# DC_DC_5V_1.net
KiCad netlist of a schematic drawn in Altium Designer
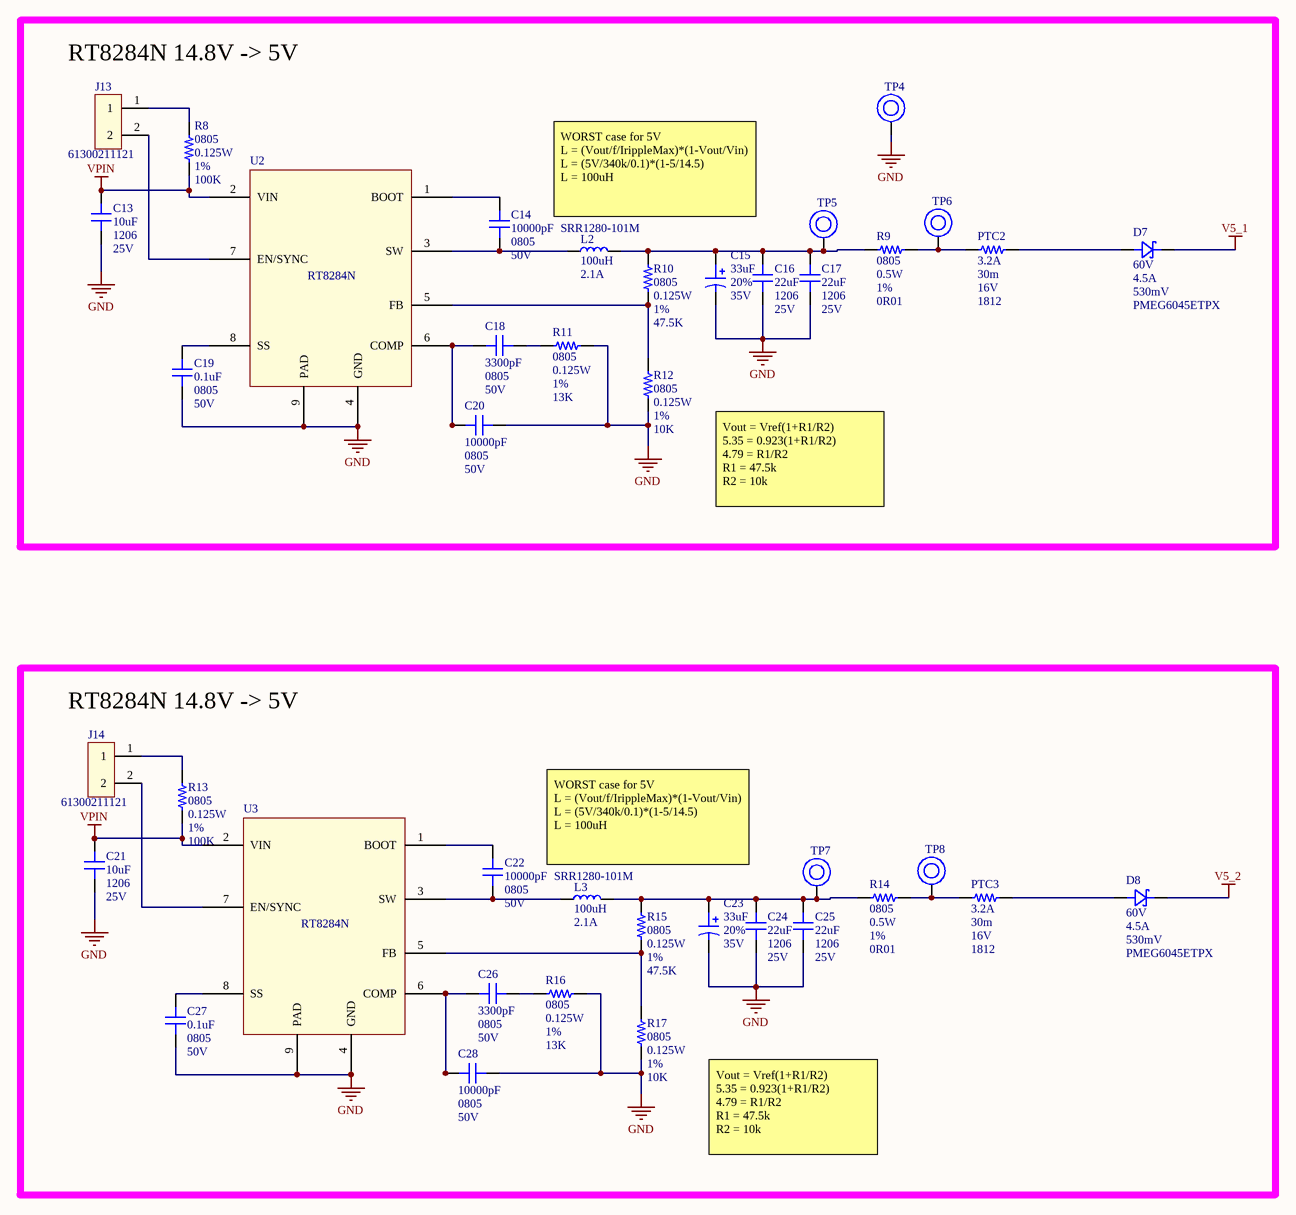
[diagram p0: DC_DC_5V_1.SchDoc]

(export (version "E")
  (design (tool "Eeschema 10.0.6"))
  (components
    (comp (ref "C13")
      (value "10uF")
      (footprint "CAP_1206")
      (description "CAP CER 10uF 25V 1206")
      (fields
        (field (name "PART NUMBER") "CL31A106KAHNFNE‎")
        (field (name "PACKAGE") "1206")
        (field (name "VOLTAGE") "25V")
        (field (name "Comment") "CAP_‎CL31A106KAHNFNE‎")
      )
      (libsource (lib "SecureBot") (part "CAP_‎CL31A106KAHNFNE‎"))
    )
    (comp (ref "C14")
      (value "10000pF")
      (footprint "CAP_0805")
      (description "CAP CER 10000pF 50V 0805")
      (fields
        (field (name "PART NUMBER") "‎CL21B103KBANNNC")
        (field (name "PACKAGE") "0805")
        (field (name "VOLTAGE") "50V")
        (field (name "Comment") "CAP_‎‎‎‎CL21B103KBANNNC")
      )
      (libsource (lib "SecureBot") (part "CAP_‎‎‎‎CL21B103KBANNNC"))
    )
    (comp (ref "C15")
      (value "33uF")
      (footprint "CAP ALU - 6.3mm DIA")
      (description "CAP ALU 33µF 35V")
      (fields
        (field (name "PART NUMBER") "EEE-FK1V330P")
        (field (name "TOLERANCE") "20%")
        (field (name "VOLTAGE") "35V")
        (field (name "Comment") "CAP_EEE-FK1V330P")
      )
      (libsource (lib "SecureBot") (part "CAP_EEE-FK1V330P"))
    )
    (comp (ref "C16")
      (value "22uF")
      (footprint "CAP_1206")
      (description "CAP CER 22uF 25V 1206")
      (fields
        (field (name "PART NUMBER") "CL31A226KAHNNNE‎")
        (field (name "PACKAGE") "1206")
        (field (name "VOLTAGE") "25V")
        (field (name "Comment") "CAP_‎‎CL31A226KAHNNNE‎")
      )
      (libsource (lib "SecureBot") (part "CAP_‎‎CL31A226KAHNNNE‎"))
    )
    (comp (ref "C17")
      (value "22uF")
      (footprint "CAP_1206")
      (description "CAP CER 22uF 25V 1206")
      (fields
        (field (name "PART NUMBER") "CL31A226KAHNNNE‎")
        (field (name "PACKAGE") "1206")
        (field (name "VOLTAGE") "25V")
        (field (name "Comment") "CAP_‎‎CL31A226KAHNNNE‎")
      )
      (libsource (lib "SecureBot") (part "CAP_‎‎CL31A226KAHNNNE‎"))
    )
    (comp (ref "C18")
      (value "3300pF")
      (footprint "CAP_0805")
      (description "CAP CER 3300pF 50V 0805")
      (fields
        (field (name "PART NUMBER") "CL21B332KBANNNC‎")
        (field (name "PACKAGE") "0805")
        (field (name "VOLTAGE") "50V")
        (field (name "Comment") "CAP_CL21B332KBANNNC‎")
      )
      (libsource (lib "SecureBot") (part "CAP_CL21B332KBANNNC‎"))
    )
    (comp (ref "C19")
      (value "0.1uF")
      (footprint "CAP_0805")
      (description "CAP CER 0.1uF 50V 0805")
      (fields
        (field (name "PART NUMBER") "CC0805KRX7R9BB104‎")
        (field (name "PACKAGE") "0805")
        (field (name "VOLTAGE") "50V")
        (field (name "Comment") "CAP_CC0805KRX7R9BB104‎")
      )
      (libsource (lib "SecureBot") (part "CAP_CC0805KRX7R9BB104‎"))
    )
    (comp (ref "C20")
      (value "10000pF")
      (footprint "CAP_0805")
      (description "CAP CER 10000pF 50V 0805")
      (fields
        (field (name "PART NUMBER") "‎CL21B103KBANNNC")
        (field (name "PACKAGE") "0805")
        (field (name "VOLTAGE") "50V")
        (field (name "Comment") "CAP_‎‎‎‎CL21B103KBANNNC")
      )
      (libsource (lib "SecureBot") (part "CAP_‎‎‎‎CL21B103KBANNNC"))
    )
    (comp (ref "C21")
      (value "10uF")
      (footprint "CAP_1206")
      (description "CAP CER 10uF 25V 1206")
      (fields
        (field (name "PART NUMBER") "CL31A106KAHNFNE‎")
        (field (name "PACKAGE") "1206")
        (field (name "VOLTAGE") "25V")
        (field (name "Comment") "CAP_‎CL31A106KAHNFNE‎")
      )
      (libsource (lib "SecureBot") (part "CAP_‎CL31A106KAHNFNE‎"))
    )
    (comp (ref "C22")
      (value "10000pF")
      (footprint "CAP_0805")
      (description "CAP CER 10000pF 50V 0805")
      (fields
        (field (name "PART NUMBER") "‎CL21B103KBANNNC")
        (field (name "PACKAGE") "0805")
        (field (name "VOLTAGE") "50V")
        (field (name "Comment") "CAP_‎‎‎‎CL21B103KBANNNC")
      )
      (libsource (lib "SecureBot") (part "CAP_‎‎‎‎CL21B103KBANNNC"))
    )
    (comp (ref "C23")
      (value "33uF")
      (footprint "CAP ALU - 6.3mm DIA")
      (description "CAP ALU 33µF 35V")
      (fields
        (field (name "PART NUMBER") "EEE-FK1V330P")
        (field (name "TOLERANCE") "20%")
        (field (name "VOLTAGE") "35V")
        (field (name "Comment") "CAP_EEE-FK1V330P")
      )
      (libsource (lib "SecureBot") (part "CAP_EEE-FK1V330P"))
    )
    (comp (ref "C24")
      (value "22uF")
      (footprint "CAP_1206")
      (description "CAP CER 22uF 25V 1206")
      (fields
        (field (name "PART NUMBER") "CL31A226KAHNNNE‎")
        (field (name "PACKAGE") "1206")
        (field (name "VOLTAGE") "25V")
        (field (name "Comment") "CAP_‎‎CL31A226KAHNNNE‎")
      )
      (libsource (lib "SecureBot") (part "CAP_‎‎CL31A226KAHNNNE‎"))
    )
    (comp (ref "C25")
      (value "22uF")
      (footprint "CAP_1206")
      (description "CAP CER 22uF 25V 1206")
      (fields
        (field (name "PART NUMBER") "CL31A226KAHNNNE‎")
        (field (name "PACKAGE") "1206")
        (field (name "VOLTAGE") "25V")
        (field (name "Comment") "CAP_‎‎CL31A226KAHNNNE‎")
      )
      (libsource (lib "SecureBot") (part "CAP_‎‎CL31A226KAHNNNE‎"))
    )
    (comp (ref "C26")
      (value "3300pF")
      (footprint "CAP_0805")
      (description "CAP CER 3300pF 50V 0805")
      (fields
        (field (name "PART NUMBER") "CL21B332KBANNNC‎")
        (field (name "PACKAGE") "0805")
        (field (name "VOLTAGE") "50V")
        (field (name "Comment") "CAP_CL21B332KBANNNC‎")
      )
      (libsource (lib "SecureBot") (part "CAP_CL21B332KBANNNC‎"))
    )
    (comp (ref "C27")
      (value "0.1uF")
      (footprint "CAP_0805")
      (description "CAP CER 0.1uF 50V 0805")
      (fields
        (field (name "PART NUMBER") "CC0805KRX7R9BB104‎")
        (field (name "PACKAGE") "0805")
        (field (name "VOLTAGE") "50V")
        (field (name "Comment") "CAP_CC0805KRX7R9BB104‎")
      )
      (libsource (lib "SecureBot") (part "CAP_CC0805KRX7R9BB104‎"))
    )
    (comp (ref "C28")
      (value "10000pF")
      (footprint "CAP_0805")
      (description "CAP CER 10000pF 50V 0805")
      (fields
        (field (name "PART NUMBER") "‎CL21B103KBANNNC")
        (field (name "PACKAGE") "0805")
        (field (name "VOLTAGE") "50V")
        (field (name "Comment") "CAP_‎‎‎‎CL21B103KBANNNC")
      )
      (libsource (lib "SecureBot") (part "CAP_‎‎‎‎CL21B103KBANNNC"))
    )
    (comp (ref "D7")
      (value "DIODE_SCH_PMEG6045ETPX")
      (footprint "DO-214AC_SOD128")
      (description "Diode Schottky 60V 4.5A Surface Mount CFP5")
      (fields
        (field (name "VOLTAGE") "60V")
        (field (name "CURRENT") "4.5A")
        (field (name "VF") "530mV")
        (field (name "PART NUMBER") "PMEG6045ETPX")
      )
      (libsource (lib "SecureBot") (part "DIODE_SCH_PMEG6045ETPX"))
    )
    (comp (ref "D8")
      (value "DIODE_SCH_PMEG6045ETPX")
      (footprint "DO-214AC_SOD128")
      (description "Diode Schottky 60V 4.5A Surface Mount CFP5")
      (fields
        (field (name "VOLTAGE") "60V")
        (field (name "CURRENT") "4.5A")
        (field (name "VF") "530mV")
        (field (name "PART NUMBER") "PMEG6045ETPX")
      )
      (libsource (lib "SecureBot") (part "DIODE_SCH_PMEG6045ETPX"))
    )
    (comp (ref "J13")
      (value "Header 2 pin SM")
      (footprint "HDR1X2")
      (fields (field (name "PART NUMBER") "61300211121"))
      (libsource (lib "SecureBot") (part "Header 2 pin SM"))
    )
    (comp (ref "J14")
      (value "Header 2 pin SM")
      (footprint "HDR1X2")
      (fields (field (name "PART NUMBER") "61300211121"))
      (libsource (lib "SecureBot") (part "Header 2 pin SM"))
    )
    (comp (ref "L2")
      (value "100uH")
      (footprint "BOURNS 12.5x12.5mm")
      (description "IND 100µH Shielded Wirewound Inductor 2.1A")
      (fields
        (field (name "TOLERANCE") "20%")
        (field (name "CURRENT") "2.1A")
        (field (name "PART NUMBER") "SRR1280-101M")
        (field (name "Comment") "IND_SRR1280-101M")
      )
      (libsource (lib "SecureBot") (part "IND_SRR1280-101M"))
    )
    (comp (ref "L3")
      (value "100uH")
      (footprint "BOURNS 12.5x12.5mm")
      (description "IND 100µH Shielded Wirewound Inductor 2.1A")
      (fields
        (field (name "TOLERANCE") "20%")
        (field (name "CURRENT") "2.1A")
        (field (name "PART NUMBER") "SRR1280-101M")
        (field (name "Comment") "IND_SRR1280-101M")
      )
      (libsource (lib "SecureBot") (part "IND_SRR1280-101M"))
    )
    (comp (ref "PTC2")
      (value "PTC_0ZCG0160BF2C")
      (footprint "PTC - 1812")
      (description "PTC_Polymeric PTC Resettable Fuse 16V 1.6A Ih")
      (fields
        (field (name "PART NUMBER") "0ZCG0160BF2C")
        (field (name "TRIP VALUE") "3.2A")
        (field (name "RES") "30m")
        (field (name "VOLTAGE") "16V")
        (field (name "PACKAGE") "1812")
      )
      (libsource (lib "SecureBot") (part "PTC_0ZCG0160BF2C"))
    )
    (comp (ref "PTC3")
      (value "PTC_0ZCG0160BF2C")
      (footprint "PTC - 1812")
      (description "PTC_Polymeric PTC Resettable Fuse 16V 1.6A Ih")
      (fields
        (field (name "PART NUMBER") "0ZCG0160BF2C")
        (field (name "TRIP VALUE") "3.2A")
        (field (name "RES") "30m")
        (field (name "VOLTAGE") "16V")
        (field (name "PACKAGE") "1812")
      )
      (libsource (lib "SecureBot") (part "PTC_0ZCG0160BF2C"))
    )
    (comp (ref "R8")
      (value "100K")
      (footprint "RES_0805")
      (description "RES 100K 1% 1/8W 0805")
      (fields
        (field (name "PART NUMBER") "‎RMCF0805FT100K‎")
        (field (name "PACKAGE") "0805")
        (field (name "POWER") "0.125W")
        (field (name "TOLERANCE") "1%")
        (field (name "Comment") "RES_‎RMCF0805FT100K‎")
      )
      (libsource (lib "SecureBot") (part "RES_‎RMCF0805FT100K‎"))
    )
    (comp (ref "R9")
      (value "0R01")
      (footprint "RES_0805")
      (description "RES 0.01R 1% 1/2W 0805")
      (fields
        (field (name "PART NUMBER") "KRL1220E-M-R010-F-T5")
        (field (name "PACKAGE") "0805")
        (field (name "POWER") "0.5W")
        (field (name "TOLERANCE") "1%")
        (field (name "Comment") "RES_‎‎‎‎‎ KRL1220E-M-R010-F-T5")
      )
      (libsource (lib "SecureBot") (part "RES_‎‎‎‎‎ KRL1220E-M-R010-F-T5"))
    )
    (comp (ref "R10")
      (value "47.5K")
      (footprint "RES_0805")
      (description "RES 47.5K 1% 1/8W 0805")
      (fields
        (field (name "PART NUMBER") "RMCF0805FT47K5‎")
        (field (name "PACKAGE") "0805")
        (field (name "POWER") "0.125W")
        (field (name "TOLERANCE") "1%")
        (field (name "Comment") "RES_‎‎RMCF0805FT47K5‎")
      )
      (libsource (lib "SecureBot") (part "RES_‎‎RMCF0805FT47K5‎"))
    )
    (comp (ref "R11")
      (value "13K")
      (footprint "RES_0805")
      (description "RES 13K 1% 1/8W 0805")
      (fields
        (field (name "PART NUMBER") "RC0805FR-0713KL")
        (field (name "PACKAGE") "0805")
        (field (name "POWER") "0.125W")
        (field (name "TOLERANCE") "1%")
        (field (name "Comment") "RES_‎ RC0805FR-0713KL")
      )
      (libsource (lib "SecureBot") (part "RES_‎ RC0805FR-0713KL"))
    )
    (comp (ref "R12")
      (value "10K")
      (footprint "RES_0805")
      (description "RES 10K 1% 1/8W 0805")
      (fields
        (field (name "PART NUMBER") "RMCF0805FT10K0")
        (field (name "PACKAGE") "0805")
        (field (name "POWER") "0.125W")
        (field (name "TOLERANCE") "1%")
        (field (name "Comment") "RES_‎RMCF0805FT10K0")
      )
      (libsource (lib "SecureBot") (part "RES_‎RMCF0805FT10K0"))
    )
    (comp (ref "R13")
      (value "100K")
      (footprint "RES_0805")
      (description "RES 100K 1% 1/8W 0805")
      (fields
        (field (name "PART NUMBER") "‎RMCF0805FT100K‎")
        (field (name "PACKAGE") "0805")
        (field (name "POWER") "0.125W")
        (field (name "TOLERANCE") "1%")
        (field (name "Comment") "RES_‎RMCF0805FT100K‎")
      )
      (libsource (lib "SecureBot") (part "RES_‎RMCF0805FT100K‎"))
    )
    (comp (ref "R14")
      (value "0R01")
      (footprint "RES_0805")
      (description "RES 0.01R 1% 1/2W 0805")
      (fields
        (field (name "PART NUMBER") "KRL1220E-M-R010-F-T5")
        (field (name "PACKAGE") "0805")
        (field (name "POWER") "0.5W")
        (field (name "TOLERANCE") "1%")
        (field (name "Comment") "RES_‎‎‎‎‎ KRL1220E-M-R010-F-T5")
      )
      (libsource (lib "SecureBot") (part "RES_‎‎‎‎‎ KRL1220E-M-R010-F-T5"))
    )
    (comp (ref "R15")
      (value "47.5K")
      (footprint "RES_0805")
      (description "RES 47.5K 1% 1/8W 0805")
      (fields
        (field (name "PART NUMBER") "RMCF0805FT47K5‎")
        (field (name "PACKAGE") "0805")
        (field (name "POWER") "0.125W")
        (field (name "TOLERANCE") "1%")
        (field (name "Comment") "RES_‎‎RMCF0805FT47K5‎")
      )
      (libsource (lib "SecureBot") (part "RES_‎‎RMCF0805FT47K5‎"))
    )
    (comp (ref "R16")
      (value "13K")
      (footprint "RES_0805")
      (description "RES 13K 1% 1/8W 0805")
      (fields
        (field (name "PART NUMBER") "RC0805FR-0713KL")
        (field (name "PACKAGE") "0805")
        (field (name "POWER") "0.125W")
        (field (name "TOLERANCE") "1%")
        (field (name "Comment") "RES_‎ RC0805FR-0713KL")
      )
      (libsource (lib "SecureBot") (part "RES_‎ RC0805FR-0713KL"))
    )
    (comp (ref "R17")
      (value "10K")
      (footprint "RES_0805")
      (description "RES 10K 1% 1/8W 0805")
      (fields
        (field (name "PART NUMBER") "RMCF0805FT10K0")
        (field (name "PACKAGE") "0805")
        (field (name "POWER") "0.125W")
        (field (name "TOLERANCE") "1%")
        (field (name "Comment") "RES_‎RMCF0805FT10K0")
      )
      (libsource (lib "SecureBot") (part "RES_‎RMCF0805FT10K0"))
    )
    (comp (ref "TP4")
      (value "TestPoint 3x3mm")
      (footprint "TestPoint 3X3mm")
      (libsource (lib "SecureBot") (part "TestPoint 3x3mm"))
    )
    (comp (ref "TP5")
      (value "TestPoint 3x3mm")
      (footprint "TestPoint 3X3mm")
      (libsource (lib "SecureBot") (part "TestPoint 3x3mm"))
    )
    (comp (ref "TP6")
      (value "TestPoint 3x3mm")
      (footprint "TestPoint 3X3mm")
      (libsource (lib "SecureBot") (part "TestPoint 3x3mm"))
    )
    (comp (ref "TP7")
      (value "TestPoint 3x3mm")
      (footprint "TestPoint 3X3mm")
      (libsource (lib "SecureBot") (part "TestPoint 3x3mm"))
    )
    (comp (ref "TP8")
      (value "TestPoint 3x3mm")
      (footprint "TestPoint 3X3mm")
      (libsource (lib "SecureBot") (part "TestPoint 3x3mm"))
    )
    (comp (ref "U2")
      (value "REG_SW_RT8284N")
      (footprint "SOP8")
      (description "REG 2A, 23V, 340kHz Synchronous Step-Down Converter")
      (fields (field (name "PART NUMBER") "RT8284N"))
      (libsource (lib "SecureBot") (part "REG_SW_RT8284N"))
    )
    (comp (ref "U3")
      (value "REG_SW_RT8284N")
      (footprint "SOP8")
      (description "REG 2A, 23V, 340kHz Synchronous Step-Down Converter")
      (fields (field (name "PART NUMBER") "RT8284N"))
      (libsource (lib "SecureBot") (part "REG_SW_RT8284N"))
    )
  )
  (nets
    (net (code "1") (name "GND") (class "Default")
      (node (ref "C13") (pin "2") (pinfunction "2_2") (pintype "passive"))
      (node (ref "C15") (pin "2") (pinfunction "2_2") (pintype "passive"))
      (node (ref "C16") (pin "2") (pinfunction "2_2") (pintype "passive"))
      (node (ref "C17") (pin "2") (pinfunction "2_2") (pintype "passive"))
      (node (ref "C19") (pin "2") (pinfunction "2_2") (pintype "passive"))
      (node (ref "C20") (pin "2") (pinfunction "2_2") (pintype "passive"))
      (node (ref "C21") (pin "2") (pinfunction "2_2") (pintype "passive"))
      (node (ref "C23") (pin "2") (pinfunction "2_2") (pintype "passive"))
      (node (ref "C24") (pin "2") (pinfunction "2_2") (pintype "passive"))
      (node (ref "C25") (pin "2") (pinfunction "2_2") (pintype "passive"))
      (node (ref "C27") (pin "2") (pinfunction "2_2") (pintype "passive"))
      (node (ref "C28") (pin "2") (pinfunction "2_2") (pintype "passive"))
      (node (ref "R11") (pin "1") (pinfunction "1_1") (pintype "passive"))
      (node (ref "R12") (pin "2") (pinfunction "2_2") (pintype "passive"))
      (node (ref "R16") (pin "2") (pinfunction "2_2") (pintype "passive"))
      (node (ref "R17") (pin "2") (pinfunction "2_2") (pintype "passive"))
      (node (ref "TP4") (pin "1") (pinfunction "1_1") (pintype "passive"))
      (node (ref "U2") (pin "4") (pinfunction "GND_4") (pintype "passive"))
      (node (ref "U2") (pin "9") (pinfunction "PAD_9") (pintype "passive"))
      (node (ref "U3") (pin "4") (pinfunction "GND_4") (pintype "passive"))
      (node (ref "U3") (pin "9") (pinfunction "PAD_9") (pintype "passive"))
    )
    (net (code "2") (name "Net-(C15-Pad1)") (class "Default")
      (node (ref "C15") (pin "1") (pinfunction "1_1") (pintype "passive"))
      (node (ref "C16") (pin "1") (pinfunction "1_1") (pintype "passive"))
      (node (ref "C17") (pin "1") (pinfunction "1_1") (pintype "passive"))
      (node (ref "L2") (pin "2") (pinfunction "2_2") (pintype "passive"))
      (node (ref "R10") (pin "1") (pinfunction "1_1") (pintype "passive"))
      (node (ref "R9") (pin "1") (pinfunction "1_1") (pintype "passive"))
      (node (ref "TP5") (pin "1") (pinfunction "1_1") (pintype "passive"))
    )
    (net (code "3") (name "Net-(C18-Pad2)") (class "Default")
      (node (ref "C18") (pin "2") (pinfunction "2_2") (pintype "passive"))
      (node (ref "R11") (pin "2") (pinfunction "2_2") (pintype "passive"))
    )
    (net (code "4") (name "Net-(C23-Pad1)") (class "Default")
      (node (ref "C23") (pin "1") (pinfunction "1_1") (pintype "passive"))
      (node (ref "C24") (pin "1") (pinfunction "1_1") (pintype "passive"))
      (node (ref "C25") (pin "1") (pinfunction "1_1") (pintype "passive"))
      (node (ref "L3") (pin "2") (pinfunction "2_2") (pintype "passive"))
      (node (ref "R14") (pin "1") (pinfunction "1_1") (pintype "passive"))
      (node (ref "R15") (pin "1") (pinfunction "1_1") (pintype "passive"))
      (node (ref "TP7") (pin "1") (pinfunction "1_1") (pintype "passive"))
    )
    (net (code "5") (name "Net-(C26-Pad2)") (class "Default")
      (node (ref "C26") (pin "2") (pinfunction "2_2") (pintype "passive"))
      (node (ref "R16") (pin "1") (pinfunction "1_1") (pintype "passive"))
    )
    (net (code "6") (name "Net-(D7-Pad1)") (class "Default")
      (node (ref "D7") (pin "1") (pinfunction "1_1") (pintype "passive"))
      (node (ref "PTC2") (pin "2") (pinfunction "2_2") (pintype "passive"))
    )
    (net (code "7") (name "Net-(D8-Pad1)") (class "Default")
      (node (ref "D8") (pin "1") (pinfunction "1_1") (pintype "passive"))
      (node (ref "PTC3") (pin "2") (pinfunction "2_2") (pintype "passive"))
    )
    (net (code "8") (name "Net-(J13-Pad1)") (class "Default")
      (node (ref "J13") (pin "1") (pinfunction "1_1") (pintype "passive"))
      (node (ref "R8") (pin "1") (pinfunction "1_1") (pintype "passive"))
    )
    (net (code "9") (name "Net-(J14-Pad1)") (class "Default")
      (node (ref "J14") (pin "1") (pinfunction "1_1") (pintype "passive"))
      (node (ref "R13") (pin "2") (pinfunction "2_2") (pintype "passive"))
    )
    (net (code "10") (name "Net-(PTC2-Pad1)") (class "Default")
      (node (ref "PTC2") (pin "1") (pinfunction "1_1") (pintype "passive"))
      (node (ref "R9") (pin "2") (pinfunction "2_2") (pintype "passive"))
      (node (ref "TP6") (pin "1") (pinfunction "1_1") (pintype "passive"))
    )
    (net (code "11") (name "Net-(PTC3-Pad1)") (class "Default")
      (node (ref "PTC3") (pin "1") (pinfunction "1_1") (pintype "passive"))
      (node (ref "R14") (pin "2") (pinfunction "2_2") (pintype "passive"))
      (node (ref "TP8") (pin "1") (pinfunction "1_1") (pintype "passive"))
    )
    (net (code "12") (name "Net-(U2-BOOT)") (class "Default")
      (node (ref "C14") (pin "1") (pinfunction "1_1") (pintype "passive"))
      (node (ref "U2") (pin "1") (pinfunction "BOOT_1") (pintype "passive"))
    )
    (net (code "13") (name "Net-(U2-COMP)") (class "Default")
      (node (ref "C18") (pin "1") (pinfunction "1_1") (pintype "passive"))
      (node (ref "C20") (pin "1") (pinfunction "1_1") (pintype "passive"))
      (node (ref "U2") (pin "6") (pinfunction "COMP_6") (pintype "passive"))
    )
    (net (code "14") (name "Net-(U2-EN{slash}SYNC)") (class "Default")
      (node (ref "J13") (pin "2") (pinfunction "2_2") (pintype "passive"))
      (node (ref "U2") (pin "7") (pinfunction "EN/SYNC_7") (pintype "passive"))
    )
    (net (code "15") (name "Net-(U2-FB)") (class "Default")
      (node (ref "R10") (pin "2") (pinfunction "2_2") (pintype "passive"))
      (node (ref "R12") (pin "1") (pinfunction "1_1") (pintype "passive"))
      (node (ref "U2") (pin "5") (pinfunction "FB_5") (pintype "passive"))
    )
    (net (code "16") (name "Net-(U2-SS)") (class "Default")
      (node (ref "C19") (pin "1") (pinfunction "1_1") (pintype "passive"))
      (node (ref "U2") (pin "8") (pinfunction "SS_8") (pintype "passive"))
    )
    (net (code "17") (name "Net-(U2-SW)") (class "Default")
      (node (ref "C14") (pin "2") (pinfunction "2_2") (pintype "passive"))
      (node (ref "L2") (pin "1") (pinfunction "1_1") (pintype "passive"))
      (node (ref "U2") (pin "3") (pinfunction "SW_3") (pintype "passive"))
    )
    (net (code "18") (name "Net-(U3-BOOT)") (class "Default")
      (node (ref "C22") (pin "1") (pinfunction "1_1") (pintype "passive"))
      (node (ref "U3") (pin "1") (pinfunction "BOOT_1") (pintype "passive"))
    )
    (net (code "19") (name "Net-(U3-COMP)") (class "Default")
      (node (ref "C26") (pin "1") (pinfunction "1_1") (pintype "passive"))
      (node (ref "C28") (pin "1") (pinfunction "1_1") (pintype "passive"))
      (node (ref "U3") (pin "6") (pinfunction "COMP_6") (pintype "passive"))
    )
    (net (code "20") (name "Net-(U3-EN{slash}SYNC)") (class "Default")
      (node (ref "J14") (pin "2") (pinfunction "2_2") (pintype "passive"))
      (node (ref "U3") (pin "7") (pinfunction "EN/SYNC_7") (pintype "passive"))
    )
    (net (code "21") (name "Net-(U3-FB)") (class "Default")
      (node (ref "R15") (pin "2") (pinfunction "2_2") (pintype "passive"))
      (node (ref "R17") (pin "1") (pinfunction "1_1") (pintype "passive"))
      (node (ref "U3") (pin "5") (pinfunction "FB_5") (pintype "passive"))
    )
    (net (code "22") (name "Net-(U3-SS)") (class "Default")
      (node (ref "C27") (pin "1") (pinfunction "1_1") (pintype "passive"))
      (node (ref "U3") (pin "8") (pinfunction "SS_8") (pintype "passive"))
    )
    (net (code "23") (name "Net-(U3-SW)") (class "Default")
      (node (ref "C22") (pin "2") (pinfunction "2_2") (pintype "passive"))
      (node (ref "L3") (pin "1") (pinfunction "1_1") (pintype "passive"))
      (node (ref "U3") (pin "3") (pinfunction "SW_3") (pintype "passive"))
    )
    (net (code "24") (name "V5_1") (class "Default")
      (node (ref "D7") (pin "2") (pinfunction "2_2") (pintype "passive"))
    )
    (net (code "25") (name "V5_2") (class "Default")
      (node (ref "D8") (pin "2") (pinfunction "2_2") (pintype "passive"))
    )
    (net (code "26") (name "VPIN") (class "Default")
      (node (ref "C13") (pin "1") (pinfunction "1_1") (pintype "passive"))
      (node (ref "C21") (pin "1") (pinfunction "1_1") (pintype "passive"))
      (node (ref "R13") (pin "1") (pinfunction "1_1") (pintype "passive"))
      (node (ref "R8") (pin "2") (pinfunction "2_2") (pintype "passive"))
      (node (ref "U2") (pin "2") (pinfunction "VIN_2") (pintype "passive"))
      (node (ref "U3") (pin "2") (pinfunction "VIN_2") (pintype "passive"))
    )
  )
)
